# ControlModuleMW.net
KiCad netlist of a schematic drawn in EAGLE
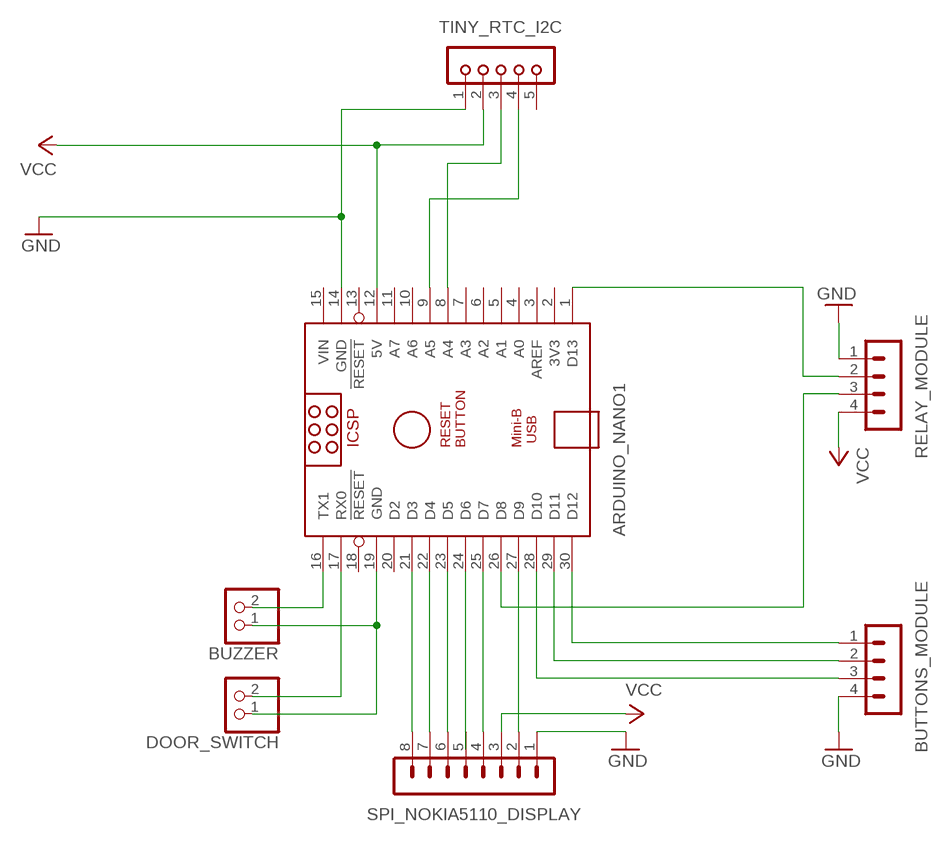
[diagram p0: schematic, sheet 1]

(export (version "E")
  (design (tool "Eeschema 10.0.6"))
  (components
    (comp (ref "ARDUINO_NANO1")
      (value "ARDUINO_NANO")
      (footprint "eagle-import:ARDUINO_NANO")
      (libsource (lib "eagle-import") (part "ARDUINO_NANO"))
    )
    (comp (ref "BUTTONS_MODULE")
      (value "MA04-1")
      (footprint "eagle-import:MA04-1")
      (libsource (lib "eagle-import") (part "MA04-1"))
    )
    (comp (ref "BUZZER")
      (value "PINHD-1X2")
      (footprint "eagle-import:1X02")
      (libsource (lib "eagle-import") (part "PINHD-1X2"))
    )
    (comp (ref "DOOR_SWITCH")
      (value "PINHD-1X2")
      (footprint "eagle-import:1X02")
      (libsource (lib "eagle-import") (part "PINHD-1X2"))
    )
    (comp (ref "RELAY_MODULE")
      (value "MA04-1")
      (footprint "eagle-import:MA04-1")
      (libsource (lib "eagle-import") (part "MA04-1"))
    )
    (comp (ref "SPI_NOKIA5110_DISPLAY")
      (value "MA08-1")
      (footprint "eagle-import:MA08-1")
      (libsource (lib "eagle-import") (part "MA08-1"))
    )
    (comp (ref "TINY_RTC_I2C")
      (value "JU05")
      (footprint "eagle-import:JU05")
      (libsource (lib "eagle-import") (part "JU05"))
    )
  )
  (nets
    (net (code "1") (name "/VIN") (class "Default")
      (node (ref "ARDUINO_NANO1") (pin "15") (pinfunction "VIN_15") (pintype "power_in"))
    )
    (net (code "2") (name "GND") (class "Default")
      (node (ref "ARDUINO_NANO1") (pin "14") (pinfunction "GND_14") (pintype "power_in"))
      (node (ref "BUTTONS_MODULE") (pin "4") (pinfunction "4_4") (pintype "passive"))
      (node (ref "RELAY_MODULE") (pin "1") (pinfunction "1_1") (pintype "passive"))
      (node (ref "SPI_NOKIA5110_DISPLAY") (pin "1") (pinfunction "1_1") (pintype "passive"))
      (node (ref "TINY_RTC_I2C") (pin "1") (pinfunction "1_1") (pintype "passive"))
    )
    (net (code "3") (name "Net-(ARDUINO_NANO1-A4)") (class "Default")
      (node (ref "ARDUINO_NANO1") (pin "8") (pinfunction "A4_8") (pintype "bidirectional"))
      (node (ref "TINY_RTC_I2C") (pin "3") (pinfunction "3_3") (pintype "passive"))
    )
    (net (code "4") (name "Net-(ARDUINO_NANO1-A5)") (class "Default")
      (node (ref "ARDUINO_NANO1") (pin "9") (pinfunction "A5_9") (pintype "bidirectional"))
      (node (ref "TINY_RTC_I2C") (pin "4") (pinfunction "4_4") (pintype "passive"))
    )
    (net (code "5") (name "Net-(ARDUINO_NANO1-D3)") (class "Default")
      (node (ref "ARDUINO_NANO1") (pin "21") (pinfunction "D3_21") (pintype "bidirectional"))
      (node (ref "SPI_NOKIA5110_DISPLAY") (pin "8") (pinfunction "8_8") (pintype "passive"))
    )
    (net (code "6") (name "Net-(ARDUINO_NANO1-D4)") (class "Default")
      (node (ref "ARDUINO_NANO1") (pin "22") (pinfunction "D4_22") (pintype "bidirectional"))
      (node (ref "SPI_NOKIA5110_DISPLAY") (pin "7") (pinfunction "7_7") (pintype "passive"))
    )
    (net (code "7") (name "Net-(ARDUINO_NANO1-D5)") (class "Default")
      (node (ref "ARDUINO_NANO1") (pin "23") (pinfunction "D5_23") (pintype "bidirectional"))
      (node (ref "SPI_NOKIA5110_DISPLAY") (pin "6") (pinfunction "6_6") (pintype "passive"))
    )
    (net (code "8") (name "Net-(ARDUINO_NANO1-D7)") (class "Default")
      (node (ref "ARDUINO_NANO1") (pin "25") (pinfunction "D7_25") (pintype "bidirectional"))
      (node (ref "SPI_NOKIA5110_DISPLAY") (pin "4") (pinfunction "4_4") (pintype "passive"))
    )
    (net (code "9") (name "Net-(ARDUINO_NANO1-D8)") (class "Default")
      (node (ref "ARDUINO_NANO1") (pin "26") (pinfunction "D8_26") (pintype "bidirectional"))
      (node (ref "RELAY_MODULE") (pin "3") (pinfunction "3_3") (pintype "passive"))
    )
    (net (code "10") (name "Net-(ARDUINO_NANO1-D9)") (class "Default")
      (node (ref "ARDUINO_NANO1") (pin "27") (pinfunction "D9_27") (pintype "bidirectional"))
      (node (ref "SPI_NOKIA5110_DISPLAY") (pin "2") (pinfunction "2_2") (pintype "passive"))
    )
    (net (code "11") (name "Net-(ARDUINO_NANO1-D10)") (class "Default")
      (node (ref "ARDUINO_NANO1") (pin "28") (pinfunction "D10_28") (pintype "bidirectional"))
      (node (ref "BUTTONS_MODULE") (pin "3") (pinfunction "3_3") (pintype "passive"))
    )
    (net (code "12") (name "Net-(ARDUINO_NANO1-D11)") (class "Default")
      (node (ref "ARDUINO_NANO1") (pin "29") (pinfunction "D11_29") (pintype "bidirectional"))
      (node (ref "BUTTONS_MODULE") (pin "2") (pinfunction "2_2") (pintype "passive"))
    )
    (net (code "13") (name "Net-(ARDUINO_NANO1-D12)") (class "Default")
      (node (ref "ARDUINO_NANO1") (pin "30") (pinfunction "D12_30") (pintype "bidirectional"))
      (node (ref "BUTTONS_MODULE") (pin "1") (pinfunction "1_1") (pintype "passive"))
    )
    (net (code "14") (name "Net-(ARDUINO_NANO1-D13)") (class "Default")
      (node (ref "ARDUINO_NANO1") (pin "1") (pinfunction "D13_1") (pintype "bidirectional"))
      (node (ref "RELAY_MODULE") (pin "2") (pinfunction "2_2") (pintype "passive"))
    )
    (net (code "15") (name "Net-(ARDUINO_NANO1-GND-Pad19)") (class "Default")
      (node (ref "ARDUINO_NANO1") (pin "19") (pinfunction "GND_19") (pintype "power_in"))
      (node (ref "BUZZER") (pin "1") (pinfunction "1_1") (pintype "passive"))
      (node (ref "DOOR_SWITCH") (pin "1") (pinfunction "1_1") (pintype "passive"))
    )
    (net (code "16") (name "Net-(ARDUINO_NANO1-RX0)") (class "Default")
      (node (ref "ARDUINO_NANO1") (pin "17") (pinfunction "RX0_17") (pintype "bidirectional"))
      (node (ref "DOOR_SWITCH") (pin "2") (pinfunction "2_2") (pintype "passive"))
    )
    (net (code "17") (name "Net-(ARDUINO_NANO1-TX1)") (class "Default")
      (node (ref "ARDUINO_NANO1") (pin "16") (pinfunction "TX1_16") (pintype "bidirectional"))
      (node (ref "BUZZER") (pin "2") (pinfunction "2_2") (pintype "passive"))
    )
    (net (code "18") (name "VCC") (class "Default")
      (node (ref "ARDUINO_NANO1") (pin "12") (pinfunction "5V_12") (pintype "power_in"))
      (node (ref "RELAY_MODULE") (pin "4") (pinfunction "4_4") (pintype "passive"))
      (node (ref "SPI_NOKIA5110_DISPLAY") (pin "3") (pinfunction "3_3") (pintype "passive"))
      (node (ref "TINY_RTC_I2C") (pin "2") (pinfunction "2_2") (pintype "passive"))
    )
    (net (code "19") (name "unconnected-(ARDUINO_NANO1-3V3-Pad2)") (class "Default")
      (node (ref "ARDUINO_NANO1") (pin "2") (pinfunction "3V3_2") (pintype "output"))
    )
    (net (code "20") (name "unconnected-(ARDUINO_NANO1-A0-Pad4)") (class "Default")
      (node (ref "ARDUINO_NANO1") (pin "4") (pinfunction "A0_4") (pintype "bidirectional"))
    )
    (net (code "21") (name "unconnected-(ARDUINO_NANO1-A1-Pad5)") (class "Default")
      (node (ref "ARDUINO_NANO1") (pin "5") (pinfunction "A1_5") (pintype "bidirectional"))
    )
    (net (code "22") (name "unconnected-(ARDUINO_NANO1-A2-Pad6)") (class "Default")
      (node (ref "ARDUINO_NANO1") (pin "6") (pinfunction "A2_6") (pintype "bidirectional"))
    )
    (net (code "23") (name "unconnected-(ARDUINO_NANO1-A3-Pad7)") (class "Default")
      (node (ref "ARDUINO_NANO1") (pin "7") (pinfunction "A3_7") (pintype "bidirectional"))
    )
    (net (code "24") (name "unconnected-(ARDUINO_NANO1-A6-Pad10)") (class "Default")
      (node (ref "ARDUINO_NANO1") (pin "10") (pinfunction "A6_10") (pintype "bidirectional"))
    )
    (net (code "25") (name "unconnected-(ARDUINO_NANO1-A7-Pad11)") (class "Default")
      (node (ref "ARDUINO_NANO1") (pin "11") (pinfunction "A7_11") (pintype "bidirectional"))
    )
    (net (code "26") (name "unconnected-(ARDUINO_NANO1-AREF-Pad3)") (class "Default")
      (node (ref "ARDUINO_NANO1") (pin "3") (pinfunction "AREF_3") (pintype "input"))
    )
    (net (code "27") (name "unconnected-(ARDUINO_NANO1-D2-Pad20)") (class "Default")
      (node (ref "ARDUINO_NANO1") (pin "20") (pinfunction "D2_20") (pintype "bidirectional"))
    )
    (net (code "28") (name "unconnected-(ARDUINO_NANO1-D6-Pad24)") (class "Default")
      (node (ref "ARDUINO_NANO1") (pin "24") (pinfunction "D6_24") (pintype "bidirectional"))
    )
    (net (code "29") (name "unconnected-(ARDUINO_NANO1-~{RESET}-Pad13)") (class "Default")
      (node (ref "ARDUINO_NANO1") (pin "13") (pinfunction "~{RESET}_13") (pintype "input"))
    )
    (net (code "30") (name "unconnected-(ARDUINO_NANO1-~{RESET}-Pad18)") (class "Default")
      (node (ref "ARDUINO_NANO1") (pin "18") (pinfunction "~{RESET}_18") (pintype "input"))
    )
    (net (code "31") (name "unconnected-(SPI_NOKIA5110_DISPLAY-Pad5)") (class "Default")
      (node (ref "SPI_NOKIA5110_DISPLAY") (pin "5") (pinfunction "5_5") (pintype "passive"))
    )
    (net (code "32") (name "unconnected-(TINY_RTC_I2C-Pad5)") (class "Default")
      (node (ref "TINY_RTC_I2C") (pin "5") (pinfunction "5_5") (pintype "passive"))
    )
  )
)
